# 6Taster_RGB-LED.net
KiCad netlist of a schematic drawn in EAGLE
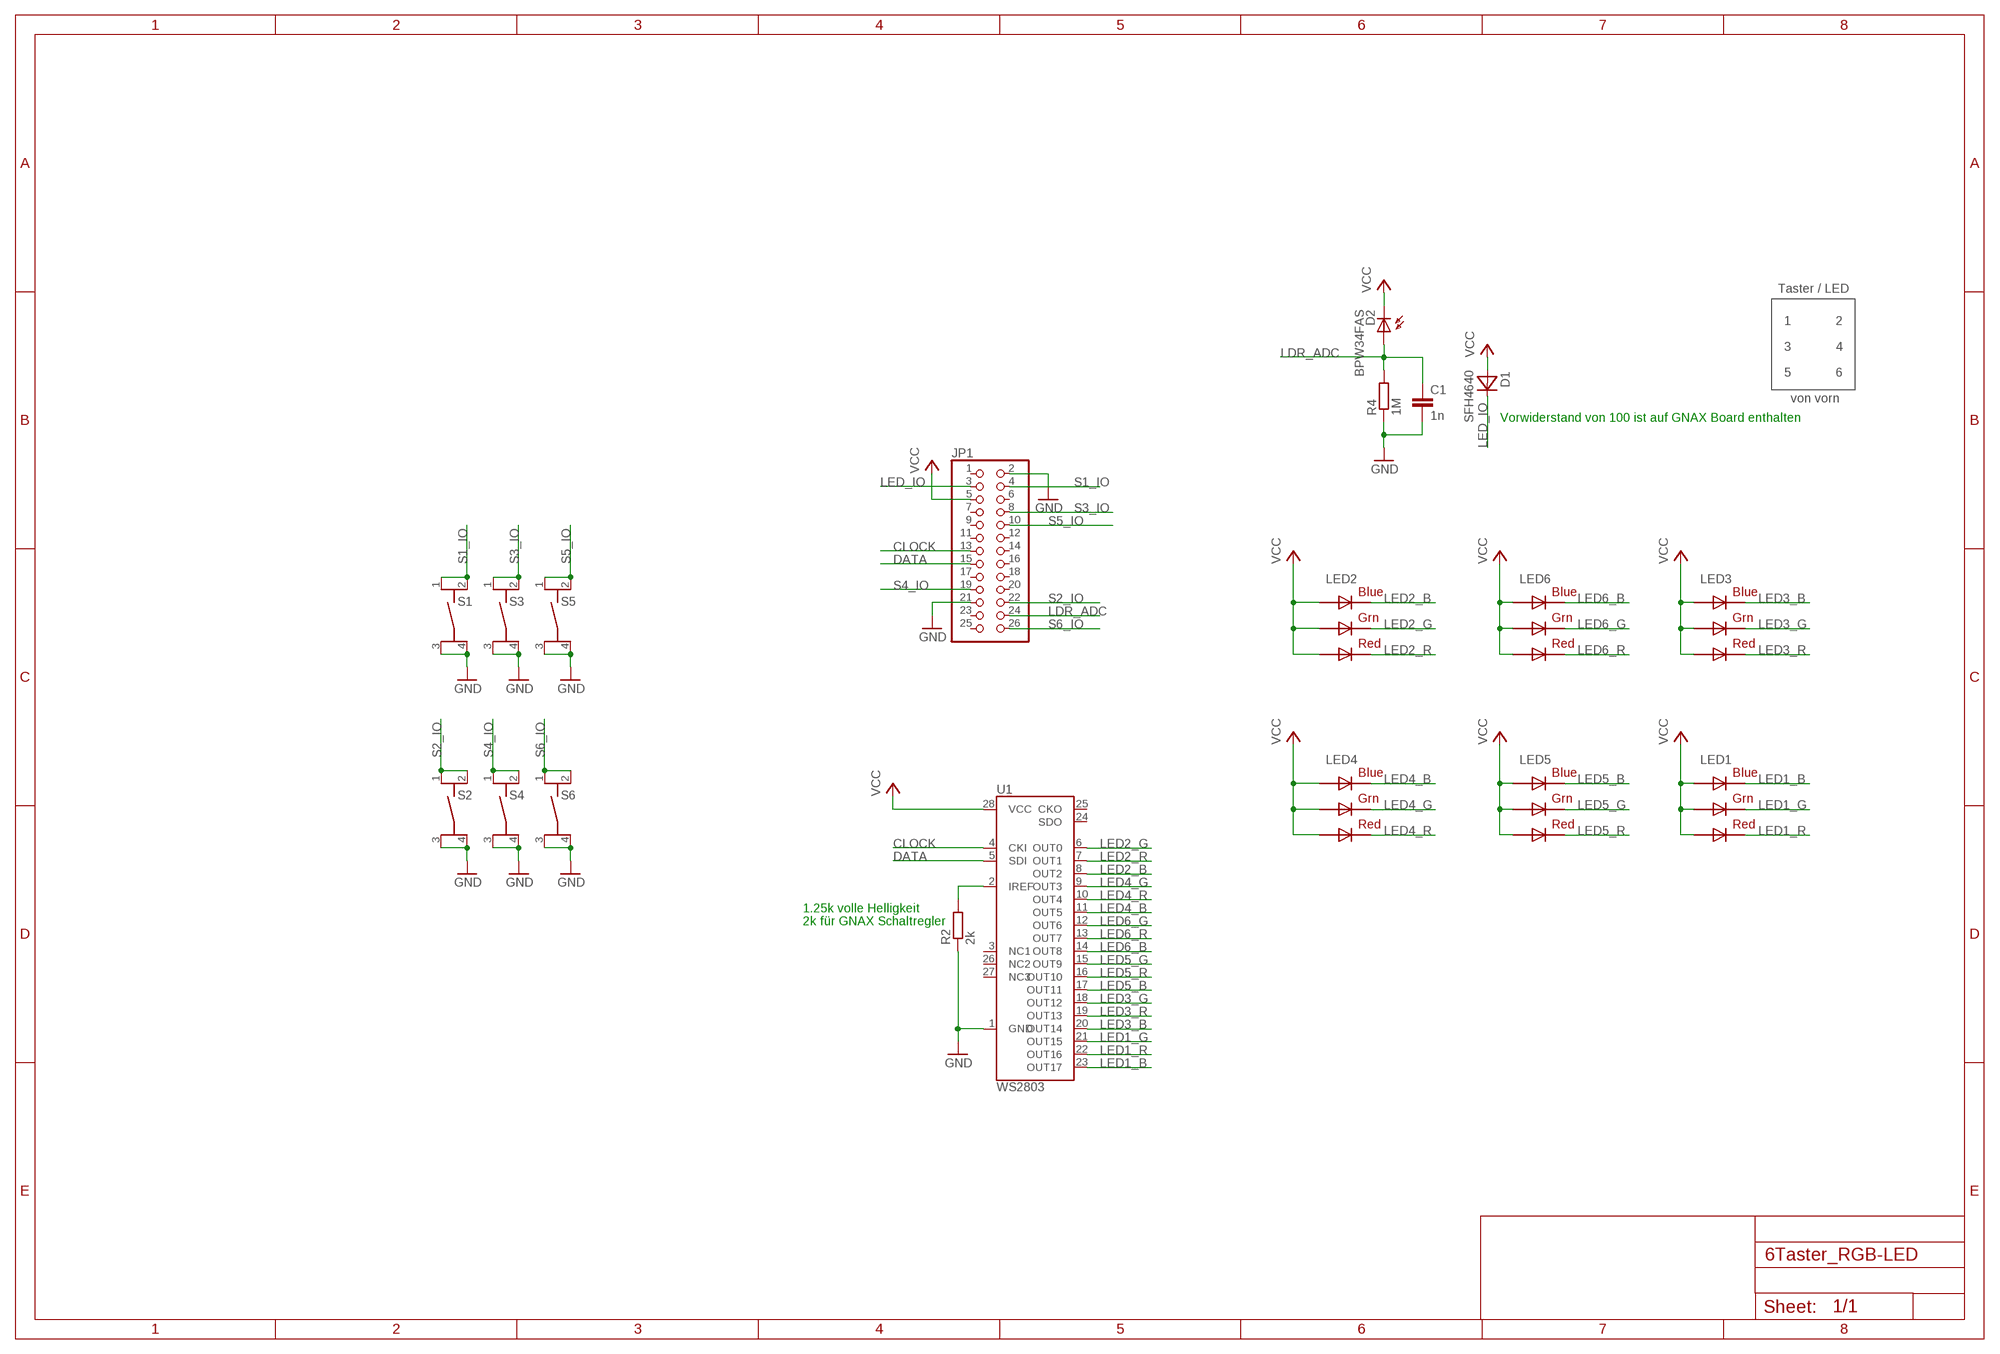
[diagram p0: schematic, sheet 1]

(export (version "E")
  (design (tool "Eeschema 10.0.6"))
  (components
    (comp (ref "C1")
      (value "1n")
      (footprint "eagle-import:C0805")
      (libsource (lib "eagle-import") (part "C-EUC0805"))
    )
    (comp (ref "D1")
      (value "SFH4640")
      (footprint "eagle-import:SFH4640")
      (libsource (lib "eagle-import") (part "SFH4640"))
    )
    (comp (ref "D2")
      (value "BPW34FAS")
      (footprint "eagle-import:BPW34FAS")
      (libsource (lib "eagle-import") (part "BPW34FAS"))
    )
    (comp (ref "JP1")
      (value "PINHD-2X13_2.54-SMD")
      (footprint "eagle-import:2X13SMD")
      (libsource (lib "eagle-import") (part "PINHD-2X13_2.54-SMD"))
    )
    (comp (ref "LED1")
      (value "RGB")
      (footprint "eagle-import:RGBLED5050")
      (libsource (lib "eagle-import") (part "RGBLED5050"))
    )
    (comp (ref "LED2")
      (value "RGB")
      (footprint "eagle-import:RGBLED5050")
      (libsource (lib "eagle-import") (part "RGBLED5050"))
    )
    (comp (ref "LED3")
      (value "RGB")
      (footprint "eagle-import:RGBLED5050")
      (libsource (lib "eagle-import") (part "RGBLED5050"))
    )
    (comp (ref "LED4")
      (value "RGB")
      (footprint "eagle-import:RGBLED5050")
      (libsource (lib "eagle-import") (part "RGBLED5050"))
    )
    (comp (ref "LED5")
      (value "RGB")
      (footprint "eagle-import:RGBLED5050")
      (libsource (lib "eagle-import") (part "RGBLED5050"))
    )
    (comp (ref "LED6")
      (value "RGB")
      (footprint "eagle-import:RGBLED5050")
      (libsource (lib "eagle-import") (part "RGBLED5050"))
    )
    (comp (ref "R2")
      (value "2k")
      (footprint "eagle-import:R0805")
      (libsource (lib "eagle-import") (part "R-EU_R0805"))
    )
    (comp (ref "R4")
      (value "1M")
      (footprint "eagle-import:R0805")
      (libsource (lib "eagle-import") (part "R-EU_R0805"))
    )
    (comp (ref "S1")
      (value "TASTER_9314SMD")
      (footprint "eagle-import:TASTER_9314")
      (libsource (lib "eagle-import") (part "TASTER_9314SMD"))
    )
    (comp (ref "S2")
      (value "TASTER_9314SMD")
      (footprint "eagle-import:TASTER_9314")
      (libsource (lib "eagle-import") (part "TASTER_9314SMD"))
    )
    (comp (ref "S3")
      (value "TASTER_9314SMD")
      (footprint "eagle-import:TASTER_9314")
      (libsource (lib "eagle-import") (part "TASTER_9314SMD"))
    )
    (comp (ref "S4")
      (value "TASTER_9314SMD")
      (footprint "eagle-import:TASTER_9314")
      (libsource (lib "eagle-import") (part "TASTER_9314SMD"))
    )
    (comp (ref "S5")
      (value "TASTER_9314SMD")
      (footprint "eagle-import:TASTER_9314")
      (libsource (lib "eagle-import") (part "TASTER_9314SMD"))
    )
    (comp (ref "S6")
      (value "TASTER_9314SMD")
      (footprint "eagle-import:TASTER_9314")
      (libsource (lib "eagle-import") (part "TASTER_9314SMD"))
    )
    (comp (ref "U1")
      (value "WS2803")
      (footprint "eagle-import:SOP-28")
      (libsource (lib "eagle-import") (part "WS2803"))
    )
  )
  (nets
    (net (code "1") (name "/CLOCK") (class "Default")
      (node (ref "JP1") (pin "13") (pinfunction "13_13") (pintype "passive"))
      (node (ref "U1") (pin "4") (pinfunction "CKI_4") (pintype "bidirectional"))
    )
    (net (code "2") (name "/DATA") (class "Default")
      (node (ref "JP1") (pin "15") (pinfunction "15_15") (pintype "passive"))
      (node (ref "U1") (pin "5") (pinfunction "SDI_5") (pintype "bidirectional"))
    )
    (net (code "3") (name "/LDR_ADC") (class "Default")
      (node (ref "C1") (pin "1") (pinfunction "1_1") (pintype "passive"))
      (node (ref "D2") (pin "ANODE") (pinfunction "A_ANODE") (pintype "passive"))
      (node (ref "JP1") (pin "24") (pinfunction "24_24") (pintype "passive"))
      (node (ref "R4") (pin "2") (pinfunction "2_2") (pintype "passive"))
    )
    (net (code "4") (name "/LED1_B") (class "Default")
      (node (ref "LED1") (pin "4") (pinfunction "BLUE_C_4") (pintype "bidirectional"))
      (node (ref "U1") (pin "23") (pinfunction "OUT17_23") (pintype "bidirectional"))
    )
    (net (code "5") (name "/LED1_G") (class "Default")
      (node (ref "LED1") (pin "6") (pinfunction "GREEN_C_6") (pintype "bidirectional"))
      (node (ref "U1") (pin "21") (pinfunction "OUT15_21") (pintype "bidirectional"))
    )
    (net (code "6") (name "/LED1_R") (class "Default")
      (node (ref "LED1") (pin "5") (pinfunction "RED_C_5") (pintype "bidirectional"))
      (node (ref "U1") (pin "22") (pinfunction "OUT16_22") (pintype "bidirectional"))
    )
    (net (code "7") (name "/LED2_B") (class "Default")
      (node (ref "LED2") (pin "4") (pinfunction "BLUE_C_4") (pintype "bidirectional"))
      (node (ref "U1") (pin "8") (pinfunction "OUT2_8") (pintype "bidirectional"))
    )
    (net (code "8") (name "/LED2_G") (class "Default")
      (node (ref "LED2") (pin "6") (pinfunction "GREEN_C_6") (pintype "bidirectional"))
      (node (ref "U1") (pin "6") (pinfunction "OUT0_6") (pintype "bidirectional"))
    )
    (net (code "9") (name "/LED2_R") (class "Default")
      (node (ref "LED2") (pin "5") (pinfunction "RED_C_5") (pintype "bidirectional"))
      (node (ref "U1") (pin "7") (pinfunction "OUT1_7") (pintype "bidirectional"))
    )
    (net (code "10") (name "/LED3_B") (class "Default")
      (node (ref "LED3") (pin "4") (pinfunction "BLUE_C_4") (pintype "bidirectional"))
      (node (ref "U1") (pin "20") (pinfunction "OUT14_20") (pintype "bidirectional"))
    )
    (net (code "11") (name "/LED3_G") (class "Default")
      (node (ref "LED3") (pin "6") (pinfunction "GREEN_C_6") (pintype "bidirectional"))
      (node (ref "U1") (pin "18") (pinfunction "OUT12_18") (pintype "bidirectional"))
    )
    (net (code "12") (name "/LED3_R") (class "Default")
      (node (ref "LED3") (pin "5") (pinfunction "RED_C_5") (pintype "bidirectional"))
      (node (ref "U1") (pin "19") (pinfunction "OUT13_19") (pintype "bidirectional"))
    )
    (net (code "13") (name "/LED4_B") (class "Default")
      (node (ref "LED4") (pin "4") (pinfunction "BLUE_C_4") (pintype "bidirectional"))
      (node (ref "U1") (pin "11") (pinfunction "OUT5_11") (pintype "bidirectional"))
    )
    (net (code "14") (name "/LED4_G") (class "Default")
      (node (ref "LED4") (pin "6") (pinfunction "GREEN_C_6") (pintype "bidirectional"))
      (node (ref "U1") (pin "9") (pinfunction "OUT3_9") (pintype "bidirectional"))
    )
    (net (code "15") (name "/LED4_R") (class "Default")
      (node (ref "LED4") (pin "5") (pinfunction "RED_C_5") (pintype "bidirectional"))
      (node (ref "U1") (pin "10") (pinfunction "OUT4_10") (pintype "bidirectional"))
    )
    (net (code "16") (name "/LED5_B") (class "Default")
      (node (ref "LED5") (pin "4") (pinfunction "BLUE_C_4") (pintype "bidirectional"))
      (node (ref "U1") (pin "17") (pinfunction "OUT11_17") (pintype "bidirectional"))
    )
    (net (code "17") (name "/LED5_G") (class "Default")
      (node (ref "LED5") (pin "6") (pinfunction "GREEN_C_6") (pintype "bidirectional"))
      (node (ref "U1") (pin "15") (pinfunction "OUT9_15") (pintype "bidirectional"))
    )
    (net (code "18") (name "/LED5_R") (class "Default")
      (node (ref "LED5") (pin "5") (pinfunction "RED_C_5") (pintype "bidirectional"))
      (node (ref "U1") (pin "16") (pinfunction "OUT10_16") (pintype "bidirectional"))
    )
    (net (code "19") (name "/LED6_B") (class "Default")
      (node (ref "LED6") (pin "4") (pinfunction "BLUE_C_4") (pintype "bidirectional"))
      (node (ref "U1") (pin "14") (pinfunction "OUT8_14") (pintype "bidirectional"))
    )
    (net (code "20") (name "/LED6_G") (class "Default")
      (node (ref "LED6") (pin "6") (pinfunction "GREEN_C_6") (pintype "bidirectional"))
      (node (ref "U1") (pin "12") (pinfunction "OUT6_12") (pintype "bidirectional"))
    )
    (net (code "21") (name "/LED6_R") (class "Default")
      (node (ref "LED6") (pin "5") (pinfunction "RED_C_5") (pintype "bidirectional"))
      (node (ref "U1") (pin "13") (pinfunction "OUT7_13") (pintype "bidirectional"))
    )
    (net (code "22") (name "/LED_IO") (class "Default")
      (node (ref "D1") (pin "KATHODE") (pinfunction "C_KATHODE") (pintype "passive"))
      (node (ref "JP1") (pin "3") (pinfunction "3_3") (pintype "passive"))
    )
    (net (code "23") (name "/S1_IO") (class "Default")
      (node (ref "JP1") (pin "4") (pinfunction "4_4") (pintype "passive"))
      (node (ref "S1") (pin "1") (pinfunction "1_1") (pintype "passive"))
      (node (ref "S1") (pin "2") (pinfunction "2_2") (pintype "passive"))
    )
    (net (code "24") (name "/S2_IO") (class "Default")
      (node (ref "JP1") (pin "22") (pinfunction "22_22") (pintype "passive"))
      (node (ref "S2") (pin "1") (pinfunction "1_1") (pintype "passive"))
      (node (ref "S2") (pin "2") (pinfunction "2_2") (pintype "passive"))
    )
    (net (code "25") (name "/S3_IO") (class "Default")
      (node (ref "JP1") (pin "8") (pinfunction "8_8") (pintype "passive"))
      (node (ref "S3") (pin "1") (pinfunction "1_1") (pintype "passive"))
      (node (ref "S3") (pin "2") (pinfunction "2_2") (pintype "passive"))
    )
    (net (code "26") (name "/S4_IO") (class "Default")
      (node (ref "JP1") (pin "19") (pinfunction "19_19") (pintype "passive"))
      (node (ref "S4") (pin "1") (pinfunction "1_1") (pintype "passive"))
      (node (ref "S4") (pin "2") (pinfunction "2_2") (pintype "passive"))
    )
    (net (code "27") (name "/S5_IO") (class "Default")
      (node (ref "JP1") (pin "10") (pinfunction "10_10") (pintype "passive"))
      (node (ref "S5") (pin "1") (pinfunction "1_1") (pintype "passive"))
      (node (ref "S5") (pin "2") (pinfunction "2_2") (pintype "passive"))
    )
    (net (code "28") (name "/S6_IO") (class "Default")
      (node (ref "JP1") (pin "26") (pinfunction "26_26") (pintype "passive"))
      (node (ref "S6") (pin "1") (pinfunction "1_1") (pintype "passive"))
      (node (ref "S6") (pin "2") (pinfunction "2_2") (pintype "passive"))
    )
    (net (code "29") (name "GND") (class "Default")
      (node (ref "C1") (pin "2") (pinfunction "2_2") (pintype "passive"))
      (node (ref "JP1") (pin "2") (pinfunction "2_2") (pintype "passive"))
      (node (ref "JP1") (pin "21") (pinfunction "21_21") (pintype "passive"))
      (node (ref "R2") (pin "1") (pinfunction "1_1") (pintype "passive"))
      (node (ref "R4") (pin "1") (pinfunction "1_1") (pintype "passive"))
      (node (ref "S1") (pin "3") (pinfunction "3_3") (pintype "passive"))
      (node (ref "S1") (pin "4") (pinfunction "4_4") (pintype "passive"))
      (node (ref "S2") (pin "3") (pinfunction "3_3") (pintype "passive"))
      (node (ref "S2") (pin "4") (pinfunction "4_4") (pintype "passive"))
      (node (ref "S3") (pin "3") (pinfunction "3_3") (pintype "passive"))
      (node (ref "S3") (pin "4") (pinfunction "4_4") (pintype "passive"))
      (node (ref "S4") (pin "3") (pinfunction "3_3") (pintype "passive"))
      (node (ref "S4") (pin "4") (pinfunction "4_4") (pintype "passive"))
      (node (ref "S5") (pin "3") (pinfunction "3_3") (pintype "passive"))
      (node (ref "S5") (pin "4") (pinfunction "4_4") (pintype "passive"))
      (node (ref "S6") (pin "3") (pinfunction "3_3") (pintype "passive"))
      (node (ref "S6") (pin "4") (pinfunction "4_4") (pintype "passive"))
      (node (ref "U1") (pin "1") (pinfunction "GND_1") (pintype "bidirectional"))
    )
    (net (code "30") (name "Net-(U1-IREF)") (class "Default")
      (node (ref "R2") (pin "2") (pinfunction "2_2") (pintype "passive"))
      (node (ref "U1") (pin "2") (pinfunction "IREF_2") (pintype "bidirectional"))
    )
    (net (code "31") (name "VCC") (class "Default")
      (node (ref "D1") (pin "ANODE") (pinfunction "A_ANODE") (pintype "passive"))
      (node (ref "D2") (pin "KATHODE") (pinfunction "C_KATHODE") (pintype "passive"))
      (node (ref "JP1") (pin "5") (pinfunction "5_5") (pintype "passive"))
      (node (ref "LED1") (pin "1") (pinfunction "GREEN_A_1") (pintype "bidirectional"))
      (node (ref "LED1") (pin "2") (pinfunction "RED_A_2") (pintype "bidirectional"))
      (node (ref "LED1") (pin "3") (pinfunction "BLUE_A_3") (pintype "bidirectional"))
      (node (ref "LED2") (pin "1") (pinfunction "GREEN_A_1") (pintype "bidirectional"))
      (node (ref "LED2") (pin "2") (pinfunction "RED_A_2") (pintype "bidirectional"))
      (node (ref "LED2") (pin "3") (pinfunction "BLUE_A_3") (pintype "bidirectional"))
      (node (ref "LED3") (pin "1") (pinfunction "GREEN_A_1") (pintype "bidirectional"))
      (node (ref "LED3") (pin "2") (pinfunction "RED_A_2") (pintype "bidirectional"))
      (node (ref "LED3") (pin "3") (pinfunction "BLUE_A_3") (pintype "bidirectional"))
      (node (ref "LED4") (pin "1") (pinfunction "GREEN_A_1") (pintype "bidirectional"))
      (node (ref "LED4") (pin "2") (pinfunction "RED_A_2") (pintype "bidirectional"))
      (node (ref "LED4") (pin "3") (pinfunction "BLUE_A_3") (pintype "bidirectional"))
      (node (ref "LED5") (pin "1") (pinfunction "GREEN_A_1") (pintype "bidirectional"))
      (node (ref "LED5") (pin "2") (pinfunction "RED_A_2") (pintype "bidirectional"))
      (node (ref "LED5") (pin "3") (pinfunction "BLUE_A_3") (pintype "bidirectional"))
      (node (ref "LED6") (pin "1") (pinfunction "GREEN_A_1") (pintype "bidirectional"))
      (node (ref "LED6") (pin "2") (pinfunction "RED_A_2") (pintype "bidirectional"))
      (node (ref "LED6") (pin "3") (pinfunction "BLUE_A_3") (pintype "bidirectional"))
      (node (ref "U1") (pin "28") (pinfunction "VCC_28") (pintype "bidirectional"))
    )
    (net (code "32") (name "unconnected-(JP1-Pad1)") (class "Default")
      (node (ref "JP1") (pin "1") (pinfunction "1_1") (pintype "passive"))
    )
    (net (code "33") (name "unconnected-(JP1-Pad6)") (class "Default")
      (node (ref "JP1") (pin "6") (pinfunction "6_6") (pintype "passive"))
    )
    (net (code "34") (name "unconnected-(JP1-Pad7)") (class "Default")
      (node (ref "JP1") (pin "7") (pinfunction "7_7") (pintype "passive"))
    )
    (net (code "35") (name "unconnected-(JP1-Pad9)") (class "Default")
      (node (ref "JP1") (pin "9") (pinfunction "9_9") (pintype "passive"))
    )
    (net (code "36") (name "unconnected-(JP1-Pad11)") (class "Default")
      (node (ref "JP1") (pin "11") (pinfunction "11_11") (pintype "passive"))
    )
    (net (code "37") (name "unconnected-(JP1-Pad12)") (class "Default")
      (node (ref "JP1") (pin "12") (pinfunction "12_12") (pintype "passive"))
    )
    (net (code "38") (name "unconnected-(JP1-Pad14)") (class "Default")
      (node (ref "JP1") (pin "14") (pinfunction "14_14") (pintype "passive"))
    )
    (net (code "39") (name "unconnected-(JP1-Pad16)") (class "Default")
      (node (ref "JP1") (pin "16") (pinfunction "16_16") (pintype "passive"))
    )
    (net (code "40") (name "unconnected-(JP1-Pad17)") (class "Default")
      (node (ref "JP1") (pin "17") (pinfunction "17_17") (pintype "passive"))
    )
    (net (code "41") (name "unconnected-(JP1-Pad18)") (class "Default")
      (node (ref "JP1") (pin "18") (pinfunction "18_18") (pintype "passive"))
    )
    (net (code "42") (name "unconnected-(JP1-Pad20)") (class "Default")
      (node (ref "JP1") (pin "20") (pinfunction "20_20") (pintype "passive"))
    )
    (net (code "43") (name "unconnected-(JP1-Pad23)") (class "Default")
      (node (ref "JP1") (pin "23") (pinfunction "23_23") (pintype "passive"))
    )
    (net (code "44") (name "unconnected-(JP1-Pad25)") (class "Default")
      (node (ref "JP1") (pin "25") (pinfunction "25_25") (pintype "passive"))
    )
    (net (code "45") (name "unconnected-(U1-CKO-Pad25)") (class "Default")
      (node (ref "U1") (pin "25") (pinfunction "CKO_25") (pintype "bidirectional"))
    )
    (net (code "46") (name "unconnected-(U1-NC1-Pad3)") (class "Default")
      (node (ref "U1") (pin "3") (pinfunction "NC1_3") (pintype "bidirectional"))
    )
    (net (code "47") (name "unconnected-(U1-NC2-Pad26)") (class "Default")
      (node (ref "U1") (pin "26") (pinfunction "NC2_26") (pintype "bidirectional"))
    )
    (net (code "48") (name "unconnected-(U1-NC3-Pad27)") (class "Default")
      (node (ref "U1") (pin "27") (pinfunction "NC3_27") (pintype "bidirectional"))
    )
    (net (code "49") (name "unconnected-(U1-SDO-Pad24)") (class "Default")
      (node (ref "U1") (pin "24") (pinfunction "SDO_24") (pintype "bidirectional"))
    )
  )
)
